# PIC24.net
KiCad netlist of a schematic drawn in Altium Designer
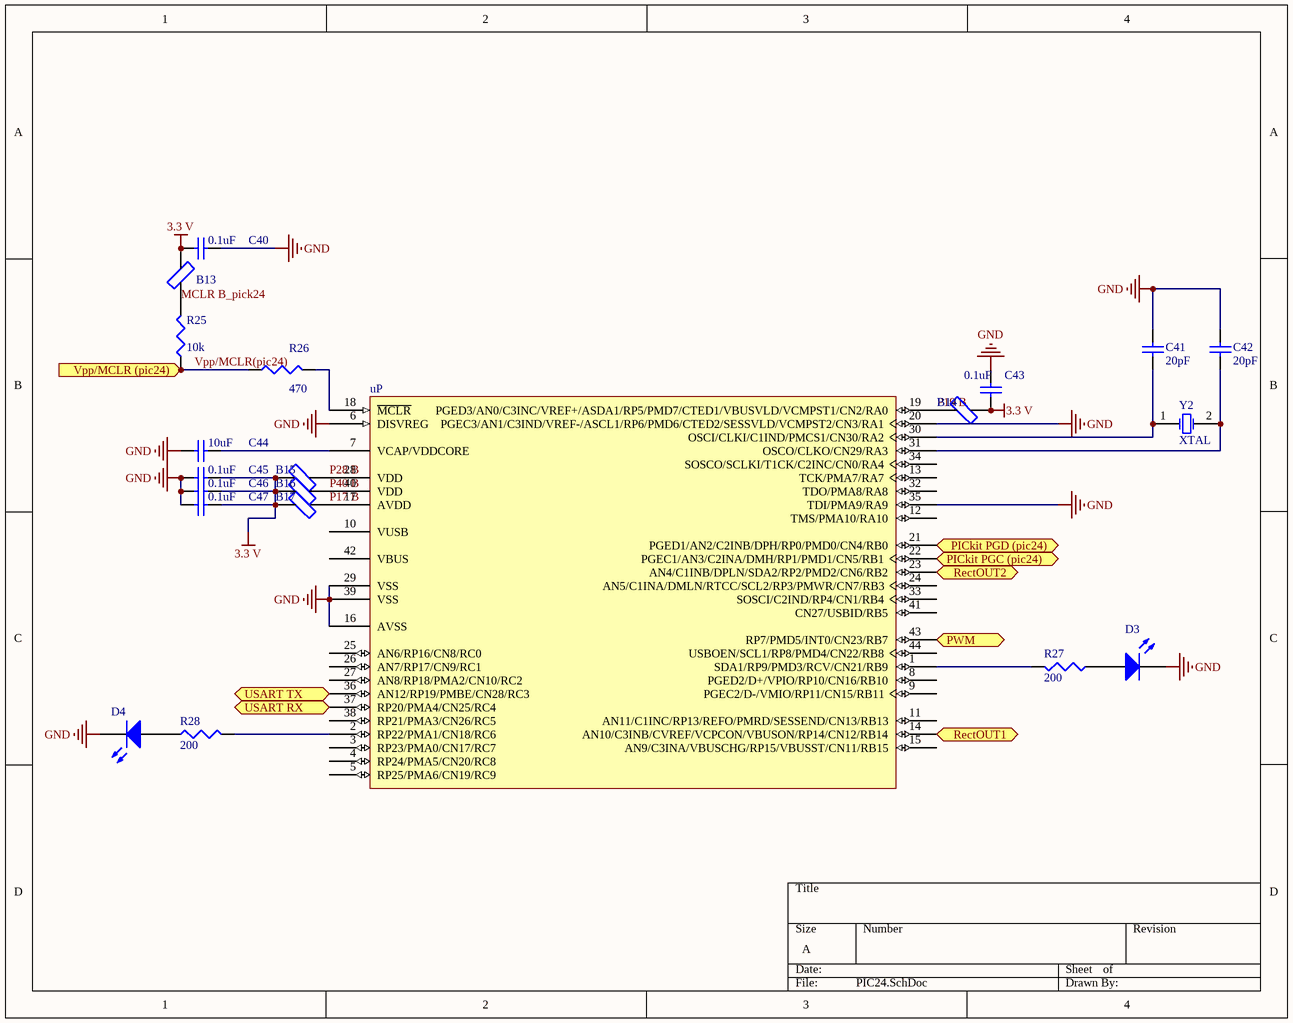
[diagram p0: PIC24.SchDoc]

(export (version "E")
  (design (tool "Eeschema 10.0.6"))
  (components
    (comp (ref "B13")
      (value "Ferrite Bead")
      (footprint "Resistor 0603")
      (libsource (lib "PMUD") (part "Ferrite Bead"))
    )
    (comp (ref "B14")
      (value "Ferrite Bead")
      (footprint "Resistor 0603")
      (libsource (lib "PMUD") (part "Ferrite Bead"))
    )
    (comp (ref "B15")
      (value "Ferrite Bead")
      (footprint "Resistor 0603")
      (libsource (lib "PMUD") (part "Ferrite Bead"))
    )
    (comp (ref "B16")
      (value "Ferrite Bead")
      (footprint "Resistor 0603")
      (libsource (lib "PMUD") (part "Ferrite Bead"))
    )
    (comp (ref "B17")
      (value "Ferrite Bead")
      (footprint "Resistor 0603")
      (libsource (lib "PMUD") (part "Ferrite Bead"))
    )
    (comp (ref "C40")
      (value "0.1uF")
      (footprint "C1206")
      (description "Capacitor (Semiconductor SIM Model)")
      (fields
        (field (name "Comment") "0.1uF 20V Ceramic Low ESR")
        (field (name "PUBLISHER") "Altium Limited")
      )
      (libsource (lib "Miscellaneous Devices") (part "Cap Semi"))
    )
    (comp (ref "C41")
      (value "20pF")
      (footprint "Capacitor 0603")
      (description "Capacitor (Semiconductor SIM Model)")
      (fields (field (name "PUBLISHER") "Altium Limited"))
      (libsource (lib "Miscellaneous Devices") (part "Cap Semi"))
    )
    (comp (ref "C42")
      (value "20pF")
      (footprint "Capacitor 0603")
      (description "Capacitor (Semiconductor SIM Model)")
      (fields (field (name "PUBLISHER") "Altium Limited"))
      (libsource (lib "Miscellaneous Devices") (part "Cap Semi"))
    )
    (comp (ref "C43")
      (value "0.1uF")
      (footprint "C1206")
      (description "Capacitor (Semiconductor SIM Model)")
      (fields
        (field (name "Comment") "0.1uF 20V Ceramic Low ESR")
        (field (name "PUBLISHER") "Altium Limited")
      )
      (libsource (lib "Miscellaneous Devices") (part "Cap Semi"))
    )
    (comp (ref "C44")
      (value "10uF")
      (footprint "Capacitor 0603")
      (description "Capacitor (Semiconductor SIM Model)")
      (fields
        (field (name "Comment") "10uF 6.3V Ceramic or Tantalum Low ESR ~5 Ohm")
        (field (name "PUBLISHER") "Altium Limited")
      )
      (libsource (lib "Miscellaneous Devices") (part "Cap Semi"))
    )
    (comp (ref "C45")
      (value "0.1uF")
      (footprint "C1206")
      (description "Capacitor (Semiconductor SIM Model)")
      (fields
        (field (name "Comment") "0.1uF 20V Ceramic Low ESR")
        (field (name "PUBLISHER") "Altium Limited")
      )
      (libsource (lib "Miscellaneous Devices") (part "Cap Semi"))
    )
    (comp (ref "C46")
      (value "0.1uF")
      (footprint "C1206")
      (description "Capacitor (Semiconductor SIM Model)")
      (fields
        (field (name "Comment") "0.1uF 20V Ceramic Low ESR")
        (field (name "PUBLISHER") "Altium Limited")
      )
      (libsource (lib "Miscellaneous Devices") (part "Cap Semi"))
    )
    (comp (ref "C47")
      (value "0.1uF")
      (footprint "C1206")
      (description "Capacitor (Semiconductor SIM Model)")
      (fields
        (field (name "Comment") "0.1uF 20V Ceramic Low ESR")
        (field (name "PUBLISHER") "Altium Limited")
      )
      (libsource (lib "Miscellaneous Devices") (part "Cap Semi"))
    )
    (comp (ref "D3")
      (value "LED2")
      (footprint "Resistor 0603")
      (description "Typical RED, GREEN, YELLOW, AMBER GaAs LED")
      (fields (field (name "PUBLISHER") "Altium Limited"))
      (libsource (lib "My Parts Sch Components") (part "LED2"))
    )
    (comp (ref "D4")
      (value "LED2")
      (footprint "Resistor 0603")
      (description "Typical RED, GREEN, YELLOW, AMBER GaAs LED")
      (fields (field (name "PUBLISHER") "Altium Limited"))
      (libsource (lib "My Parts Sch Components") (part "LED2"))
    )
    (comp (ref "R25")
      (value "10k")
      (footprint "Capacitor 0603")
      (description "Resistor")
      (fields (field (name "Comment") "1/16 w 10K ohms 1%") (field (name "PUBLISHER") "Altium Limited"))
      (libsource (lib "CustomParts_MattW") (part "Res3"))
    )
    (comp (ref "R26")
      (value "470")
      (footprint "Capacitor 0603")
      (description "Resistor")
      (fields (field (name "PUBLISHER") "Altium Limited"))
      (libsource (lib "CustomParts_MattW") (part "Res3"))
    )
    (comp (ref "R27")
      (value "200")
      (footprint "Capacitor 0603")
      (description "Resistor")
      (fields (field (name "Comment") "200 ohms 1%") (field (name "PUBLISHER") "Altium Limited"))
      (libsource (lib "CustomParts_MattW") (part "Res3"))
    )
    (comp (ref "R28")
      (value "200")
      (footprint "Capacitor 0603")
      (description "Resistor")
      (fields (field (name "Comment") "200 ohms 1%") (field (name "PUBLISHER") "Altium Limited"))
      (libsource (lib "CustomParts_MattW") (part "Res3"))
    )
    (comp (ref "uP")
      (value "PIC24FJ32GB004-I/PT")
      (footprint "TQFP-PT44_L")
      (fields (field (name "PUBLISHER") "Altium Limited"))
      (libsource (lib "Microchip Microcontroller 16-Bit PIC24F") (part "PIC24FJ32GB004-I/PT"))
    )
    (comp (ref "Y2")
      (value "XTAL")
      (footprint "SMD Oscillator")
      (description "Crystal Oscillator")
      (fields (field (name "PUBLISHER") "Altium Limited"))
      (libsource (lib "Miscellaneous Devices") (part "XTAL"))
    )
  )
  (nets
    (net (code "1") (name "/MCLR B_pick24") (class "Default")
      (node (ref "B13") (pin "1") (pinfunction "1_1") (pintype "passive"))
      (node (ref "R25") (pin "2") (pinfunction "2_2") (pintype "passive"))
    )
    (net (code "2") (name "/P17 B") (class "Default")
      (node (ref "B17") (pin "2") (pinfunction "2_2") (pintype "passive"))
      (node (ref "uP") (pin "17") (pinfunction "AVDD_17") (pintype "power_in"))
    )
    (net (code "3") (name "/P19 B") (class "Default")
      (node (ref "B14") (pin "1") (pinfunction "1_1") (pintype "passive"))
      (node (ref "uP") (pin "19") (pinfunction "PGED3/AN0/C3INC/VREF+/ASDA1/RP5/PMD7/CTED1/VBUSVLD/VCMPST1/CN2/RA0_19") (pintype "bidirectional"))
    )
    (net (code "4") (name "/P28 B") (class "Default")
      (node (ref "B15") (pin "2") (pinfunction "2_2") (pintype "passive"))
      (node (ref "uP") (pin "28") (pinfunction "VDD_28") (pintype "power_in"))
    )
    (net (code "5") (name "/P40 B") (class "Default")
      (node (ref "B16") (pin "2") (pinfunction "2_2") (pintype "passive"))
      (node (ref "uP") (pin "40") (pinfunction "VDD_40") (pintype "power_in"))
    )
    (net (code "6") (name "/PICkit PGC (pic24)") (class "Default")
      (node (ref "uP") (pin "22") (pinfunction "PGEC1/AN3/C2INA/DMH/RP1/PMD1/CN5/RB1_22") (pintype "bidirectional"))
    )
    (net (code "7") (name "/PICkit PGD (pic24)") (class "Default")
      (node (ref "uP") (pin "21") (pinfunction "PGED1/AN2/C2INB/DPH/RP0/PMD0/CN4/RB0_21") (pintype "bidirectional"))
    )
    (net (code "8") (name "/PWM") (class "Default")
      (node (ref "uP") (pin "43") (pinfunction "RP7/PMD5/INT0/CN23/RB7_43") (pintype "bidirectional"))
    )
    (net (code "9") (name "/RectOUT1") (class "Default")
      (node (ref "uP") (pin "14") (pinfunction "AN10/C3INB/CVREF/VCPCON/VBUSON/RP14/CN12/RB14_14") (pintype "bidirectional"))
    )
    (net (code "10") (name "/RectOUT2") (class "Default")
      (node (ref "uP") (pin "23") (pinfunction "AN4/C1INB/DPLN/SDA2/RP2/PMD2/CN6/RB2_23") (pintype "bidirectional"))
    )
    (net (code "11") (name "/USART RX") (class "Default")
      (node (ref "uP") (pin "37") (pinfunction "RP20/PMA4/CN25/RC4_37") (pintype "bidirectional"))
    )
    (net (code "12") (name "/USART TX") (class "Default")
      (node (ref "uP") (pin "36") (pinfunction "AN12/RP19/PMBE/CN28/RC3_36") (pintype "bidirectional"))
    )
    (net (code "13") (name "/Vpp{slash}MCLR(pic24)") (class "Default")
      (node (ref "R25") (pin "1") (pinfunction "1_1") (pintype "passive"))
      (node (ref "R26") (pin "1") (pinfunction "1_1") (pintype "passive"))
    )
    (net (code "14") (name "3.3 V") (class "Default")
      (node (ref "B13") (pin "2") (pinfunction "2_2") (pintype "passive"))
      (node (ref "B14") (pin "2") (pinfunction "2_2") (pintype "passive"))
      (node (ref "B15") (pin "1") (pinfunction "1_1") (pintype "passive"))
      (node (ref "B16") (pin "1") (pinfunction "1_1") (pintype "passive"))
      (node (ref "B17") (pin "1") (pinfunction "1_1") (pintype "passive"))
      (node (ref "C40") (pin "2") (pinfunction "2_2") (pintype "passive"))
      (node (ref "C43") (pin "2") (pinfunction "2_2") (pintype "passive"))
      (node (ref "C45") (pin "1") (pinfunction "1_1") (pintype "passive"))
      (node (ref "C46") (pin "1") (pinfunction "1_1") (pintype "passive"))
      (node (ref "C47") (pin "1") (pinfunction "1_1") (pintype "passive"))
    )
    (net (code "15") (name "GND") (class "Default")
      (node (ref "C40") (pin "1") (pinfunction "1_1") (pintype "passive"))
      (node (ref "C41") (pin "1") (pinfunction "1_1") (pintype "passive"))
      (node (ref "C42") (pin "1") (pinfunction "1_1") (pintype "passive"))
      (node (ref "C43") (pin "1") (pinfunction "1_1") (pintype "passive"))
      (node (ref "C44") (pin "2") (pinfunction "2_2") (pintype "passive"))
      (node (ref "C45") (pin "2") (pinfunction "2_2") (pintype "passive"))
      (node (ref "C46") (pin "2") (pinfunction "2_2") (pintype "passive"))
      (node (ref "C47") (pin "2") (pinfunction "2_2") (pintype "passive"))
      (node (ref "D3") (pin "2") (pinfunction "K_2") (pintype "passive"))
      (node (ref "D4") (pin "2") (pinfunction "K_2") (pintype "passive"))
      (node (ref "uP") (pin "16") (pinfunction "AVSS_16") (pintype "power_in"))
      (node (ref "uP") (pin "20") (pinfunction "PGEC3/AN1/C3IND/VREF-/ASCL1/RP6/PMD6/CTED2/SESSVLD/VCMPST2/CN3/RA1_20") (pintype "bidirectional"))
      (node (ref "uP") (pin "29") (pinfunction "VSS_29") (pintype "power_in"))
      (node (ref "uP") (pin "35") (pinfunction "TDI/PMA9/RA9_35") (pintype "bidirectional"))
      (node (ref "uP") (pin "39") (pinfunction "VSS_39") (pintype "power_in"))
      (node (ref "uP") (pin "6") (pinfunction "DISVREG_6") (pintype "input"))
    )
    (net (code "16") (name "Net-(D3-A)") (class "Default")
      (node (ref "D3") (pin "1") (pinfunction "A_1") (pintype "passive"))
      (node (ref "R27") (pin "1") (pinfunction "1_1") (pintype "passive"))
    )
    (net (code "17") (name "Net-(D4-A)") (class "Default")
      (node (ref "D4") (pin "1") (pinfunction "A_1") (pintype "passive"))
      (node (ref "R28") (pin "1") (pinfunction "1_1") (pintype "passive"))
    )
    (net (code "18") (name "Net-(Y2-OSC1)") (class "Default")
      (node (ref "C41") (pin "2") (pinfunction "2_2") (pintype "passive"))
      (node (ref "Y2") (pin "1") (pinfunction "OSC1_1") (pintype "passive"))
      (node (ref "uP") (pin "30") (pinfunction "OSCI/CLKI/C1IND/PMCS1/CN30/RA2_30") (pintype "bidirectional"))
    )
    (net (code "19") (name "Net-(Y2-OSC2)") (class "Default")
      (node (ref "C42") (pin "2") (pinfunction "2_2") (pintype "passive"))
      (node (ref "Y2") (pin "2") (pinfunction "OSC2_2") (pintype "passive"))
      (node (ref "uP") (pin "31") (pinfunction "OSCO/CLKO/CN29/RA3_31") (pintype "bidirectional"))
    )
    (net (code "20") (name "Net-(uP-RP22{slash}PMA1{slash}CN18{slash}RC6)") (class "Default")
      (node (ref "R28") (pin "2") (pinfunction "2_2") (pintype "passive"))
      (node (ref "uP") (pin "2") (pinfunction "RP22/PMA1/CN18/RC6_2") (pintype "bidirectional"))
    )
    (net (code "21") (name "Net-(uP-SDA1{slash}RP9{slash}PMD3{slash}RCV{slash}CN21{slash}RB9)") (class "Default")
      (node (ref "R27") (pin "2") (pinfunction "2_2") (pintype "passive"))
      (node (ref "uP") (pin "1") (pinfunction "SDA1/RP9/PMD3/RCV/CN21/RB9_1") (pintype "bidirectional"))
    )
    (net (code "22") (name "Net-(uP-VCAP{slash}VDDCORE)") (class "Default")
      (node (ref "C44") (pin "1") (pinfunction "1_1") (pintype "passive"))
      (node (ref "uP") (pin "7") (pinfunction "VCAP/VDDCORE_7") (pintype "power_in"))
    )
    (net (code "23") (name "Net-(uP-~{MCLR})") (class "Default")
      (node (ref "R26") (pin "2") (pinfunction "2_2") (pintype "passive"))
      (node (ref "uP") (pin "18") (pinfunction "~{MCLR}_18") (pintype "input"))
    )
    (net (code "24") (name "unconnected-(uP-AN5{slash}C1INA{slash}DMLN{slash}RTCC{slash}SCL2{slash}RP3{slash}PMWR{slash}CN7{slash}RB3-Pad24)") (class "Default")
      (node (ref "uP") (pin "24") (pinfunction "AN5/C1INA/DMLN/RTCC/SCL2/RP3/PMWR/CN7/RB3_24") (pintype "bidirectional"))
    )
    (net (code "25") (name "unconnected-(uP-AN6{slash}RP16{slash}CN8{slash}RC0-Pad25)") (class "Default")
      (node (ref "uP") (pin "25") (pinfunction "AN6/RP16/CN8/RC0_25") (pintype "bidirectional"))
    )
    (net (code "26") (name "unconnected-(uP-AN7{slash}RP17{slash}CN9{slash}RC1-Pad26)") (class "Default")
      (node (ref "uP") (pin "26") (pinfunction "AN7/RP17/CN9/RC1_26") (pintype "bidirectional"))
    )
    (net (code "27") (name "unconnected-(uP-AN8{slash}RP18{slash}PMA2{slash}CN10{slash}RC2-Pad27)") (class "Default")
      (node (ref "uP") (pin "27") (pinfunction "AN8/RP18/PMA2/CN10/RC2_27") (pintype "bidirectional"))
    )
    (net (code "28") (name "unconnected-(uP-AN9{slash}C3INA{slash}VBUSCHG{slash}RP15{slash}VBUSST{slash}CN11{slash}RB15-Pad15)") (class "Default")
      (node (ref "uP") (pin "15") (pinfunction "AN9/C3INA/VBUSCHG/RP15/VBUSST/CN11/RB15_15") (pintype "bidirectional"))
    )
    (net (code "29") (name "unconnected-(uP-AN11{slash}C1INC{slash}RP13{slash}REFO{slash}PMRD{slash}SESSEND{slash}CN13{slash}RB13-Pad11)") (class "Default")
      (node (ref "uP") (pin "11") (pinfunction "AN11/C1INC/RP13/REFO/PMRD/SESSEND/CN13/RB13_11") (pintype "bidirectional"))
    )
    (net (code "30") (name "unconnected-(uP-CN27{slash}USBID{slash}RB5-Pad41)") (class "Default")
      (node (ref "uP") (pin "41") (pinfunction "CN27/USBID/RB5_41") (pintype "bidirectional"))
    )
    (net (code "31") (name "unconnected-(uP-PGEC2{slash}D-{slash}VMIO{slash}RP11{slash}CN15{slash}RB11-Pad9)") (class "Default")
      (node (ref "uP") (pin "9") (pinfunction "PGEC2/D-/VMIO/RP11/CN15/RB11_9") (pintype "bidirectional"))
    )
    (net (code "32") (name "unconnected-(uP-PGED2{slash}D+{slash}VPIO{slash}RP10{slash}CN16{slash}RB10-Pad8)") (class "Default")
      (node (ref "uP") (pin "8") (pinfunction "PGED2/D+/VPIO/RP10/CN16/RB10_8") (pintype "bidirectional"))
    )
    (net (code "33") (name "unconnected-(uP-RP21{slash}PMA3{slash}CN26{slash}RC5-Pad38)") (class "Default")
      (node (ref "uP") (pin "38") (pinfunction "RP21/PMA3/CN26/RC5_38") (pintype "bidirectional"))
    )
    (net (code "34") (name "unconnected-(uP-RP23{slash}PMA0{slash}CN17{slash}RC7-Pad3)") (class "Default")
      (node (ref "uP") (pin "3") (pinfunction "RP23/PMA0/CN17/RC7_3") (pintype "bidirectional"))
    )
    (net (code "35") (name "unconnected-(uP-RP24{slash}PMA5{slash}CN20{slash}RC8-Pad4)") (class "Default")
      (node (ref "uP") (pin "4") (pinfunction "RP24/PMA5/CN20/RC8_4") (pintype "bidirectional"))
    )
    (net (code "36") (name "unconnected-(uP-RP25{slash}PMA6{slash}CN19{slash}RC9-Pad5)") (class "Default")
      (node (ref "uP") (pin "5") (pinfunction "RP25/PMA6/CN19/RC9_5") (pintype "bidirectional"))
    )
    (net (code "37") (name "unconnected-(uP-SOSCI{slash}C2IND{slash}RP4{slash}CN1{slash}RB4-Pad33)") (class "Default")
      (node (ref "uP") (pin "33") (pinfunction "SOSCI/C2IND/RP4/CN1/RB4_33") (pintype "bidirectional"))
    )
    (net (code "38") (name "unconnected-(uP-SOSCO{slash}SCLKI{slash}T1CK{slash}C2INC{slash}CN0{slash}RA4-Pad34)") (class "Default")
      (node (ref "uP") (pin "34") (pinfunction "SOSCO/SCLKI/T1CK/C2INC/CN0/RA4_34") (pintype "bidirectional"))
    )
    (net (code "39") (name "unconnected-(uP-TCK{slash}PMA7{slash}RA7-Pad13)") (class "Default")
      (node (ref "uP") (pin "13") (pinfunction "TCK/PMA7/RA7_13") (pintype "bidirectional"))
    )
    (net (code "40") (name "unconnected-(uP-TDO{slash}PMA8{slash}RA8-Pad32)") (class "Default")
      (node (ref "uP") (pin "32") (pinfunction "TDO/PMA8/RA8_32") (pintype "bidirectional"))
    )
    (net (code "41") (name "unconnected-(uP-TMS{slash}PMA10{slash}RA10-Pad12)") (class "Default")
      (node (ref "uP") (pin "12") (pinfunction "TMS/PMA10/RA10_12") (pintype "bidirectional"))
    )
    (net (code "42") (name "unconnected-(uP-USBOEN{slash}SCL1{slash}RP8{slash}PMD4{slash}CN22{slash}RB8-Pad44)") (class "Default")
      (node (ref "uP") (pin "44") (pinfunction "USBOEN/SCL1/RP8/PMD4/CN22/RB8_44") (pintype "bidirectional"))
    )
    (net (code "43") (name "unconnected-(uP-VBUS-Pad42)") (class "Default")
      (node (ref "uP") (pin "42") (pinfunction "VBUS_42") (pintype "power_in"))
    )
    (net (code "44") (name "unconnected-(uP-VUSB-Pad10)") (class "Default")
      (node (ref "uP") (pin "10") (pinfunction "VUSB_10") (pintype "power_in"))
    )
  )
)
